# LPC1768_2.net
KiCad netlist of a schematic drawn in Altium Designer
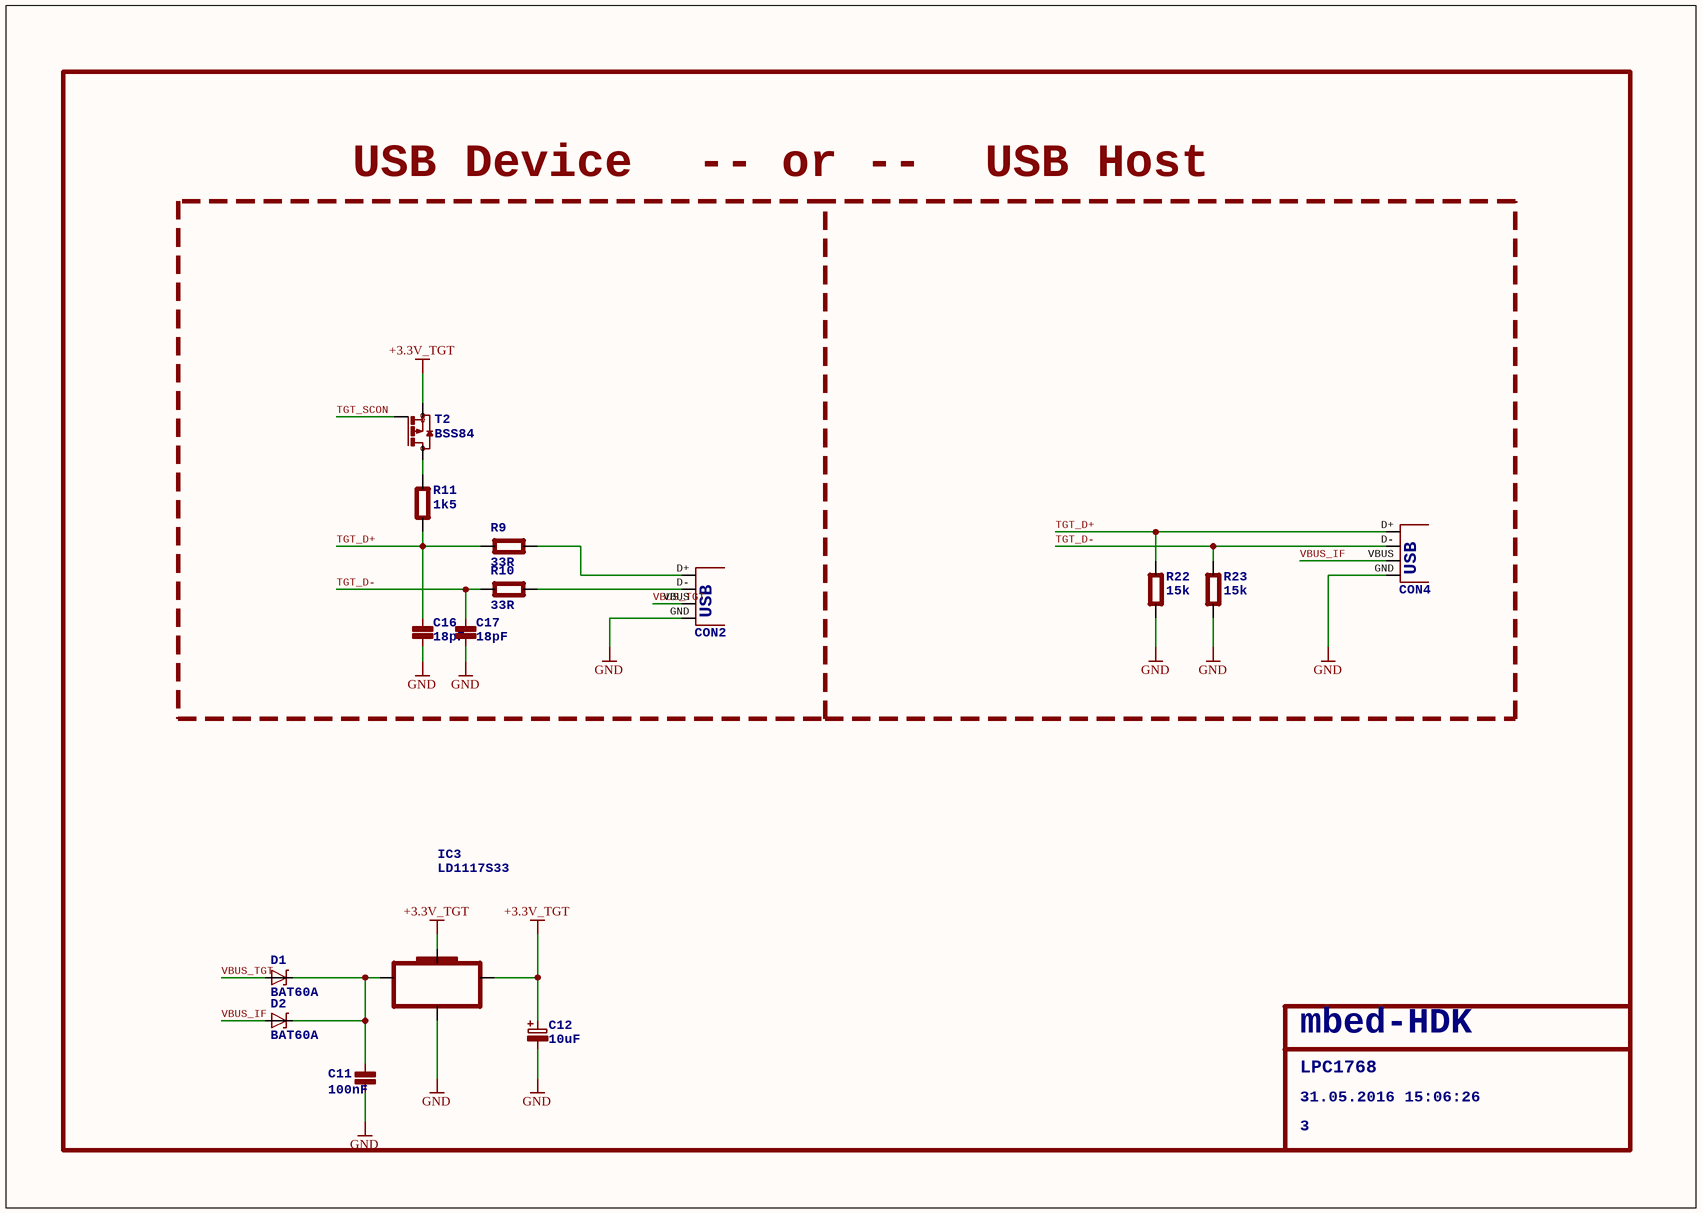
[diagram p0: LPC1768_2.SchDoc]

(export (version "E")
  (design (tool "Eeschema 10.0.6"))
  (components
    (comp (ref "C11") (value "100nF") (footprint "0603") (libsource (lib "mbed-HDK") (part "C0603")))
    (comp (ref "C12") (value "10uF") (footprint "CASE-B") (libsource (lib "mbed-HDK") (part "C-POLB")))
    (comp (ref "C16") (value "18pF") (footprint "0603") (libsource (lib "mbed-HDK") (part "C0603")))
    (comp (ref "C17") (value "18pF") (footprint "0603") (libsource (lib "mbed-HDK") (part "C0603")))
    (comp (ref "CON2")
      (value "USB-MB-S")
      (footprint "USB-MB-S")
      (description "USB Connectors")
      (fields (field (name "USB") "USB"))
      (libsource (lib "mbed-HDK") (part "USB-MB-S"))
    )
    (comp (ref "CON4")
      (value "USB-A-H")
      (footprint "USB-A-H")
      (description "USB Connectors")
      (fields (field (name "USB") "USB"))
      (libsource (lib "mbed-HDK") (part "USB-A-H"))
    )
    (comp (ref "D1") (value "BAT60A") (footprint "BAT60A") (libsource (lib "mbed-HDK") (part "BAT60A")))
    (comp (ref "D2") (value "BAT60A") (footprint "BAT60A") (libsource (lib "mbed-HDK") (part "BAT60A")))
    (comp (ref "IC3")
      (value "LD1117S33")
      (footprint "SOT223")
      (description "VOLTAGE REGULATOR SMD 3,3V")
      (libsource (lib "mbed-HDK") (part "LD1117S33"))
    )
    (comp (ref "R9") (value "33R") (footprint "0603") (libsource (lib "mbed-HDK") (part "R0603")))
    (comp (ref "R10") (value "33R") (footprint "0603") (libsource (lib "mbed-HDK") (part "R0603")))
    (comp (ref "R11") (value "1k5") (footprint "0603") (libsource (lib "mbed-HDK") (part "R0603")))
    (comp (ref "R22") (value "15k") (footprint "0603") (libsource (lib "mbed-HDK") (part "R0603")))
    (comp (ref "R23") (value "15k") (footprint "0603") (libsource (lib "mbed-HDK") (part "R0603")))
    (comp (ref "T2")
      (value "BSS84")
      (footprint "SOT23")
      (description "P-CHANNEL MOS FET")
      (libsource (lib "mbed-HDK") (part "BSS84"))
    )
  )
  (nets
    (net (code "1") (name "+3.3V_TGT") (class "Default")
      (node (ref "C12") (pin "1") (pinfunction "1_1") (pintype "passive"))
      (node (ref "IC3") (pin "2") (pinfunction "OUT_2") (pintype "passive"))
      (node (ref "IC3") (pin "4") (pinfunction "K_4") (pintype "passive"))
      (node (ref "T2") (pin "2") (pinfunction "S_2") (pintype "passive"))
    )
    (net (code "2") (name "/TGT_D+") (class "Default")
      (node (ref "C16") (pin "1") (pinfunction "P$1_1") (pintype "passive"))
      (node (ref "CON4") (pin "D+") (pinfunction "D+_D+") (pintype "passive"))
      (node (ref "R11") (pin "2") (pinfunction "P$2_2") (pintype "passive"))
      (node (ref "R22") (pin "2") (pinfunction "P$2_2") (pintype "passive"))
      (node (ref "R9") (pin "1") (pinfunction "P$1_1") (pintype "passive"))
    )
    (net (code "3") (name "/TGT_D-") (class "Default")
      (node (ref "C17") (pin "1") (pinfunction "P$1_1") (pintype "passive"))
      (node (ref "CON4") (pin "D-") (pinfunction "D-_D-") (pintype "passive"))
      (node (ref "R10") (pin "1") (pinfunction "P$1_1") (pintype "passive"))
      (node (ref "R23") (pin "2") (pinfunction "P$2_2") (pintype "passive"))
    )
    (net (code "4") (name "/TGT_SCON") (class "Default")
      (node (ref "T2") (pin "1") (pinfunction "G_1") (pintype "passive"))
    )
    (net (code "5") (name "/VBUS_IF") (class "Default")
      (node (ref "CON4") (pin "VBUS") (pinfunction "VBUS_VBUS") (pintype "passive"))
      (node (ref "D2") (pin "A") (pinfunction "A_A") (pintype "passive"))
    )
    (net (code "6") (name "/VBUS_TGT") (class "Default")
      (node (ref "CON2") (pin "VBUS") (pinfunction "VBUS_VBUS") (pintype "passive"))
      (node (ref "D1") (pin "A") (pinfunction "A_A") (pintype "passive"))
    )
    (net (code "7") (name "GND") (class "Default")
      (node (ref "C11") (pin "2") (pinfunction "P$2_2") (pintype "passive"))
      (node (ref "C12") (pin "2") (pinfunction "2_2") (pintype "passive"))
      (node (ref "C16") (pin "2") (pinfunction "P$2_2") (pintype "passive"))
      (node (ref "C17") (pin "2") (pinfunction "P$2_2") (pintype "passive"))
      (node (ref "CON2") (pin "GND") (pinfunction "GND_GND") (pintype "passive"))
      (node (ref "CON4") (pin "GND") (pinfunction "GND_GND") (pintype "passive"))
      (node (ref "IC3") (pin "1") (pinfunction "GND_1") (pintype "passive"))
      (node (ref "R22") (pin "1") (pinfunction "P$1_1") (pintype "passive"))
      (node (ref "R23") (pin "1") (pinfunction "P$1_1") (pintype "passive"))
    )
    (net (code "8") (name "Net-(C11-P$1)") (class "Default")
      (node (ref "C11") (pin "1") (pinfunction "P$1_1") (pintype "passive"))
      (node (ref "D1") (pin "K") (pinfunction "K_K") (pintype "passive"))
      (node (ref "D2") (pin "K") (pinfunction "K_K") (pintype "passive"))
      (node (ref "IC3") (pin "3") (pinfunction "IN_3") (pintype "passive"))
    )
    (net (code "9") (name "Net-(R9-P$2)") (class "Default")
      (node (ref "CON2") (pin "D+") (pinfunction "D+_D+") (pintype "passive"))
      (node (ref "R9") (pin "2") (pinfunction "P$2_2") (pintype "passive"))
    )
    (net (code "10") (name "Net-(R10-P$2)") (class "Default")
      (node (ref "CON2") (pin "D-") (pinfunction "D-_D-") (pintype "passive"))
      (node (ref "R10") (pin "2") (pinfunction "P$2_2") (pintype "passive"))
    )
    (net (code "11") (name "Net-(R11-P$1)") (class "Default")
      (node (ref "R11") (pin "1") (pinfunction "P$1_1") (pintype "passive"))
      (node (ref "T2") (pin "3") (pinfunction "D_3") (pintype "passive"))
    )
  )
)
